# amplifier_ckt.net
KiCad netlist of a schematic drawn in EAGLE
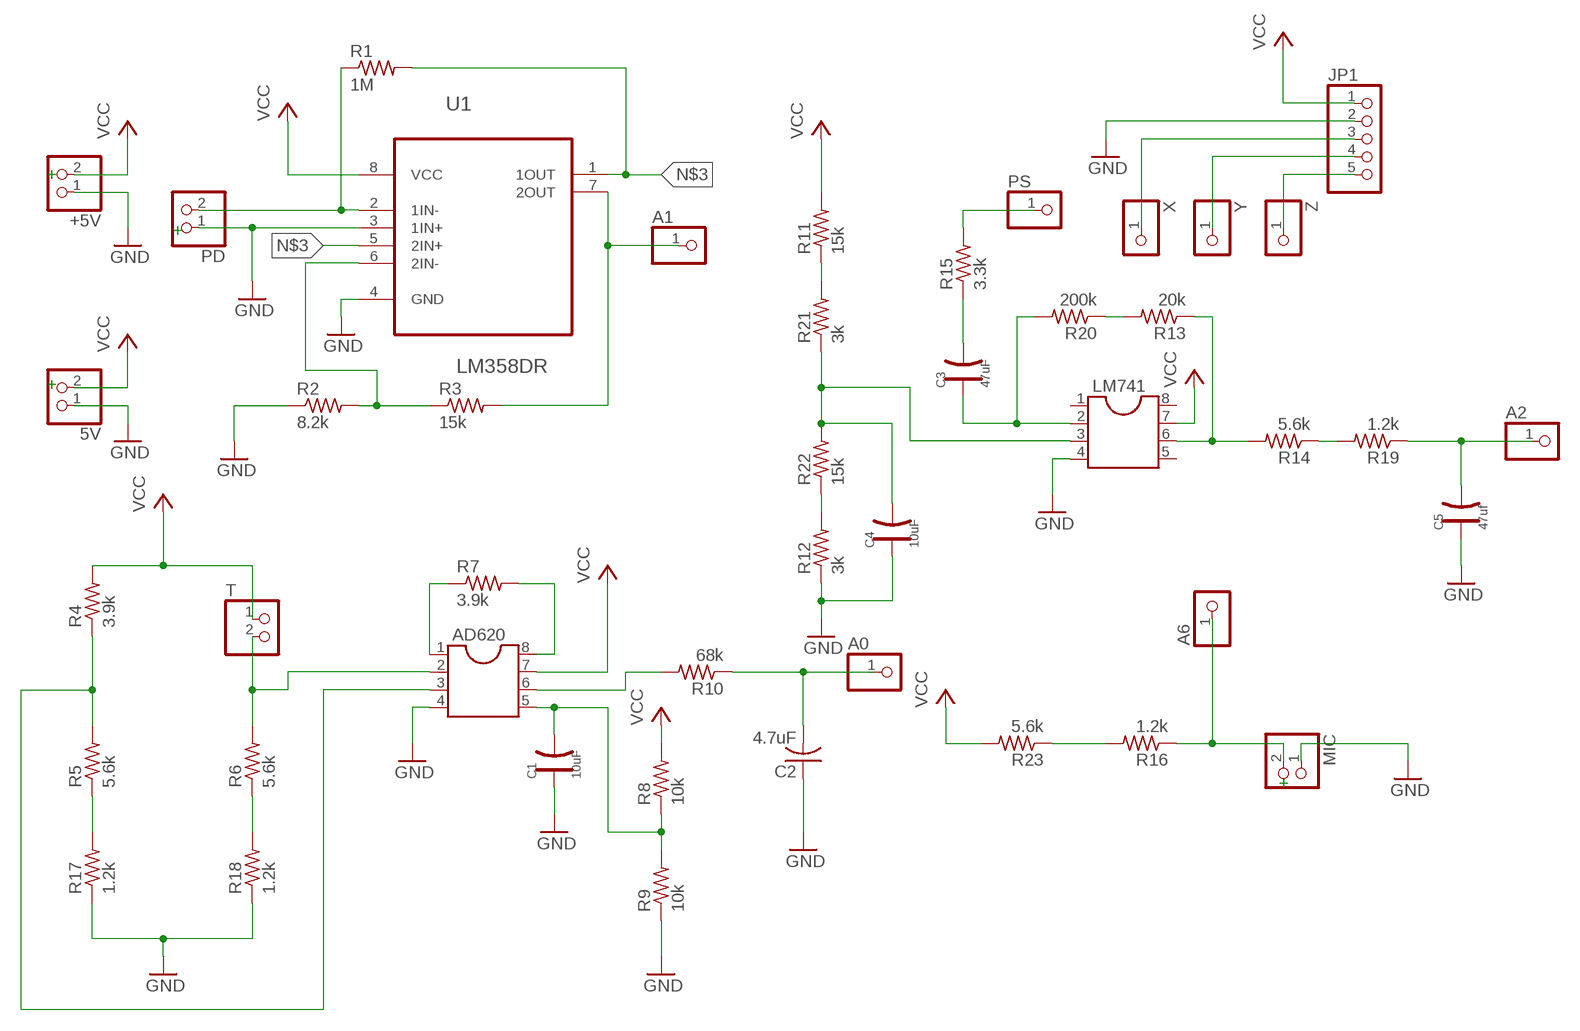
[diagram p0: schematic, sheet 1]

(export (version "E")
  (design (tool "Eeschema 10.0.6"))
  (components
    (comp (ref "+5V")
      (value "PINHD-1X2")
      (footprint "eagle-import:1X02")
      (libsource (lib "eagle-import") (part "PINHD-1X2"))
    )
    (comp (ref "5V")
      (value "PINHD-1X2")
      (footprint "eagle-import:1X02")
      (libsource (lib "eagle-import") (part "PINHD-1X2"))
    )
    (comp (ref "A0")
      (value "PINHD-1X1")
      (footprint "eagle-import:1X01")
      (libsource (lib "eagle-import") (part "PINHD-1X1"))
    )
    (comp (ref "A1")
      (value "PINHD-1X1")
      (footprint "eagle-import:1X01")
      (libsource (lib "eagle-import") (part "PINHD-1X1"))
    )
    (comp (ref "A2")
      (value "PINHD-1X1")
      (footprint "eagle-import:1X01")
      (libsource (lib "eagle-import") (part "PINHD-1X1"))
    )
    (comp (ref "A6")
      (value "PINHD-1X1")
      (footprint "eagle-import:1X01")
      (libsource (lib "eagle-import") (part "PINHD-1X1"))
    )
    (comp (ref "AD620")
      (value "DIL8S")
      (footprint "eagle-import:SOCKET-08")
      (libsource (lib "eagle-import") (part "DIL8S"))
    )
    (comp (ref "C1")
      (value "10uF")
      (footprint "eagle-import:AVX-B")
      (libsource (lib "eagle-import") (part "CAP-POLAR-AVX-B"))
    )
    (comp (ref "C2")
      (value "4.7uF")
      (footprint "eagle-import:C0805")
      (libsource (lib "eagle-import") (part "C-USC0805"))
    )
    (comp (ref "C3")
      (value "47uF")
      (footprint "eagle-import:AVX-B")
      (libsource (lib "eagle-import") (part "CAP-POLAR-AVX-B"))
    )
    (comp (ref "C4")
      (value "10uF")
      (footprint "eagle-import:AVX-B")
      (libsource (lib "eagle-import") (part "CAP-POLAR-AVX-B"))
    )
    (comp (ref "C5")
      (value "47uf")
      (footprint "eagle-import:AVX-B")
      (libsource (lib "eagle-import") (part "CAP-POLAR-AVX-B"))
    )
    (comp (ref "JP1")
      (value "PINHD-1X5")
      (footprint "eagle-import:1X05")
      (libsource (lib "eagle-import") (part "PINHD-1X5"))
    )
    (comp (ref "LM741")
      (value "DIL8S")
      (footprint "eagle-import:SOCKET-08")
      (libsource (lib "eagle-import") (part "DIL8S"))
    )
    (comp (ref "MIC")
      (value "PINHD-1X2")
      (footprint "eagle-import:1X02")
      (libsource (lib "eagle-import") (part "PINHD-1X2"))
    )
    (comp (ref "PD")
      (value "PINHD-1X2")
      (footprint "eagle-import:1X02")
      (libsource (lib "eagle-import") (part "PINHD-1X2"))
    )
    (comp (ref "PS")
      (value "PINHD-1X1")
      (footprint "eagle-import:1X01")
      (libsource (lib "eagle-import") (part "PINHD-1X1"))
    )
    (comp (ref "R1")
      (value "1M")
      (footprint "eagle-import:R0603")
      (libsource (lib "eagle-import") (part "R-US_R0603"))
    )
    (comp (ref "R2")
      (value "8.2k")
      (footprint "eagle-import:R0603")
      (libsource (lib "eagle-import") (part "R-US_R0603"))
    )
    (comp (ref "R3")
      (value "15k")
      (footprint "eagle-import:R0603")
      (libsource (lib "eagle-import") (part "R-US_R0603"))
    )
    (comp (ref "R4")
      (value "3.9k")
      (footprint "eagle-import:R0603")
      (libsource (lib "eagle-import") (part "R-US_R0603"))
    )
    (comp (ref "R5")
      (value "5.6k")
      (footprint "eagle-import:R0603")
      (libsource (lib "eagle-import") (part "R-US_R0603"))
    )
    (comp (ref "R6")
      (value "5.6k")
      (footprint "eagle-import:R0603")
      (libsource (lib "eagle-import") (part "R-US_R0603"))
    )
    (comp (ref "R7")
      (value "3.9k")
      (footprint "eagle-import:R0603")
      (libsource (lib "eagle-import") (part "R-US_R0603"))
    )
    (comp (ref "R8")
      (value "10k")
      (footprint "eagle-import:R0603")
      (libsource (lib "eagle-import") (part "R-US_R0603"))
    )
    (comp (ref "R9")
      (value "10k")
      (footprint "eagle-import:R0603")
      (libsource (lib "eagle-import") (part "R-US_R0603"))
    )
    (comp (ref "R10")
      (value "68k")
      (footprint "eagle-import:R0603")
      (libsource (lib "eagle-import") (part "R-US_R0603"))
    )
    (comp (ref "R11")
      (value "15k")
      (footprint "eagle-import:R0603")
      (libsource (lib "eagle-import") (part "R-US_R0603"))
    )
    (comp (ref "R12")
      (value "3k")
      (footprint "eagle-import:R0603")
      (libsource (lib "eagle-import") (part "R-US_R0603"))
    )
    (comp (ref "R13")
      (value "20k")
      (footprint "eagle-import:R0603")
      (libsource (lib "eagle-import") (part "R-US_R0603"))
    )
    (comp (ref "R14")
      (value "5.6k")
      (footprint "eagle-import:R0603")
      (libsource (lib "eagle-import") (part "R-US_R0603"))
    )
    (comp (ref "R15")
      (value "3.3k")
      (footprint "eagle-import:R0603")
      (libsource (lib "eagle-import") (part "R-US_R0603"))
    )
    (comp (ref "R16")
      (value "1.2k")
      (footprint "eagle-import:R0603")
      (libsource (lib "eagle-import") (part "R-US_R0603"))
    )
    (comp (ref "R17")
      (value "1.2k")
      (footprint "eagle-import:R0603")
      (libsource (lib "eagle-import") (part "R-US_R0603"))
    )
    (comp (ref "R18")
      (value "1.2k")
      (footprint "eagle-import:R0603")
      (libsource (lib "eagle-import") (part "R-US_R0603"))
    )
    (comp (ref "R19")
      (value "1.2k")
      (footprint "eagle-import:R0603")
      (libsource (lib "eagle-import") (part "R-US_R0603"))
    )
    (comp (ref "R20")
      (value "200k")
      (footprint "eagle-import:R0603")
      (libsource (lib "eagle-import") (part "R-US_R0603"))
    )
    (comp (ref "R21")
      (value "3k")
      (footprint "eagle-import:R0603")
      (libsource (lib "eagle-import") (part "R-US_R0603"))
    )
    (comp (ref "R22")
      (value "15k")
      (footprint "eagle-import:R0603")
      (libsource (lib "eagle-import") (part "R-US_R0603"))
    )
    (comp (ref "R23")
      (value "5.6k")
      (footprint "eagle-import:R0603")
      (libsource (lib "eagle-import") (part "R-US_R0603"))
    )
    (comp (ref "T")
      (value "PINHD-1X2")
      (footprint "eagle-import:1X02")
      (libsource (lib "eagle-import") (part "PINHD-1X2"))
    )
    (comp (ref "U1")
      (value "LM358DR")
      (footprint "eagle-import:SOIC127P600X175-8N")
      (libsource (lib "eagle-import") (part "LM358DR"))
    )
    (comp (ref "X")
      (value "PINHD-1X1")
      (footprint "eagle-import:1X01")
      (libsource (lib "eagle-import") (part "PINHD-1X1"))
    )
    (comp (ref "Y")
      (value "PINHD-1X1")
      (footprint "eagle-import:1X01")
      (libsource (lib "eagle-import") (part "PINHD-1X1"))
    )
    (comp (ref "Z")
      (value "PINHD-1X1")
      (footprint "eagle-import:1X01")
      (libsource (lib "eagle-import") (part "PINHD-1X1"))
    )
  )
  (nets
    (net (code "1") (name "GND") (class "Default")
      (node (ref "+5V") (pin "1") (pinfunction "1_1") (pintype "passive"))
      (node (ref "5V") (pin "1") (pinfunction "1_1") (pintype "passive"))
      (node (ref "AD620") (pin "4") (pinfunction "4_4") (pintype "passive"))
      (node (ref "C1") (pin "+") (pinfunction "+_+") (pintype "passive"))
      (node (ref "C2") (pin "1") (pinfunction "1_1") (pintype "passive"))
      (node (ref "C4") (pin "+") (pinfunction "+_+") (pintype "passive"))
      (node (ref "C5") (pin "+") (pinfunction "+_+") (pintype "passive"))
      (node (ref "JP1") (pin "2") (pinfunction "2_2") (pintype "passive"))
      (node (ref "LM741") (pin "4") (pinfunction "4_4") (pintype "passive"))
      (node (ref "MIC") (pin "1") (pinfunction "1_1") (pintype "passive"))
      (node (ref "PD") (pin "1") (pinfunction "1_1") (pintype "passive"))
      (node (ref "R12") (pin "1") (pinfunction "1_1") (pintype "passive"))
      (node (ref "R17") (pin "1") (pinfunction "1_1") (pintype "passive"))
      (node (ref "R18") (pin "1") (pinfunction "1_1") (pintype "passive"))
      (node (ref "R2") (pin "1") (pinfunction "1_1") (pintype "passive"))
      (node (ref "R9") (pin "1") (pinfunction "1_1") (pintype "passive"))
      (node (ref "U1") (pin "3") (pinfunction "1IN+_3") (pintype "input"))
      (node (ref "U1") (pin "4") (pinfunction "GND_4") (pintype "passive"))
    )
    (net (code "2") (name "N$3") (class "Default")
      (node (ref "R1") (pin "2") (pinfunction "2_2") (pintype "passive"))
      (node (ref "U1") (pin "1") (pinfunction "1OUT_1") (pintype "output"))
      (node (ref "U1") (pin "5") (pinfunction "2IN+_5") (pintype "input"))
    )
    (net (code "3") (name "Net-(A0-Pad1)") (class "Default")
      (node (ref "A0") (pin "1") (pinfunction "1_1") (pintype "passive"))
      (node (ref "C2") (pin "2") (pinfunction "2_2") (pintype "passive"))
      (node (ref "R10") (pin "1") (pinfunction "1_1") (pintype "passive"))
    )
    (net (code "4") (name "Net-(A2-Pad1)") (class "Default")
      (node (ref "A2") (pin "1") (pinfunction "1_1") (pintype "passive"))
      (node (ref "C5") (pin "-") (pinfunction "-_-") (pintype "passive"))
      (node (ref "R19") (pin "1") (pinfunction "1_1") (pintype "passive"))
    )
    (net (code "5") (name "Net-(A6-Pad1)") (class "Default")
      (node (ref "A6") (pin "1") (pinfunction "1_1") (pintype "passive"))
      (node (ref "MIC") (pin "2") (pinfunction "2_2") (pintype "passive"))
      (node (ref "R16") (pin "1") (pinfunction "1_1") (pintype "passive"))
    )
    (net (code "6") (name "Net-(AD620-Pad1)") (class "Default")
      (node (ref "AD620") (pin "1") (pinfunction "1_1") (pintype "passive"))
      (node (ref "R7") (pin "1") (pinfunction "1_1") (pintype "passive"))
    )
    (net (code "7") (name "Net-(AD620-Pad2)") (class "Default")
      (node (ref "AD620") (pin "2") (pinfunction "2_2") (pintype "passive"))
      (node (ref "R6") (pin "2") (pinfunction "2_2") (pintype "passive"))
      (node (ref "T") (pin "2") (pinfunction "2_2") (pintype "passive"))
    )
    (net (code "8") (name "Net-(AD620-Pad3)") (class "Default")
      (node (ref "AD620") (pin "3") (pinfunction "3_3") (pintype "passive"))
      (node (ref "R4") (pin "1") (pinfunction "1_1") (pintype "passive"))
      (node (ref "R5") (pin "2") (pinfunction "2_2") (pintype "passive"))
    )
    (net (code "9") (name "Net-(AD620-Pad5)") (class "Default")
      (node (ref "AD620") (pin "5") (pinfunction "5_5") (pintype "passive"))
      (node (ref "C1") (pin "-") (pinfunction "-_-") (pintype "passive"))
      (node (ref "R8") (pin "1") (pinfunction "1_1") (pintype "passive"))
      (node (ref "R9") (pin "2") (pinfunction "2_2") (pintype "passive"))
    )
    (net (code "10") (name "Net-(AD620-Pad6)") (class "Default")
      (node (ref "AD620") (pin "6") (pinfunction "6_6") (pintype "passive"))
      (node (ref "R10") (pin "2") (pinfunction "2_2") (pintype "passive"))
    )
    (net (code "11") (name "Net-(AD620-Pad8)") (class "Default")
      (node (ref "AD620") (pin "8") (pinfunction "8_8") (pintype "passive"))
      (node (ref "R7") (pin "2") (pinfunction "2_2") (pintype "passive"))
    )
    (net (code "12") (name "Net-(C3-Pad+)") (class "Default")
      (node (ref "C3") (pin "+") (pinfunction "+_+") (pintype "passive"))
      (node (ref "LM741") (pin "2") (pinfunction "2_2") (pintype "passive"))
      (node (ref "R20") (pin "2") (pinfunction "2_2") (pintype "passive"))
    )
    (net (code "13") (name "Net-(C3-Pad-)") (class "Default")
      (node (ref "C3") (pin "-") (pinfunction "-_-") (pintype "passive"))
      (node (ref "R15") (pin "1") (pinfunction "1_1") (pintype "passive"))
    )
    (net (code "14") (name "Net-(C4-Pad-)") (class "Default")
      (node (ref "C4") (pin "-") (pinfunction "-_-") (pintype "passive"))
      (node (ref "LM741") (pin "3") (pinfunction "3_3") (pintype "passive"))
      (node (ref "R21") (pin "1") (pinfunction "1_1") (pintype "passive"))
      (node (ref "R22") (pin "2") (pinfunction "2_2") (pintype "passive"))
    )
    (net (code "15") (name "Net-(JP1-Pad3)") (class "Default")
      (node (ref "JP1") (pin "3") (pinfunction "3_3") (pintype "passive"))
      (node (ref "X") (pin "1") (pinfunction "1_1") (pintype "passive"))
    )
    (net (code "16") (name "Net-(JP1-Pad4)") (class "Default")
      (node (ref "JP1") (pin "4") (pinfunction "4_4") (pintype "passive"))
      (node (ref "Y") (pin "1") (pinfunction "1_1") (pintype "passive"))
    )
    (net (code "17") (name "Net-(JP1-Pad5)") (class "Default")
      (node (ref "JP1") (pin "5") (pinfunction "5_5") (pintype "passive"))
      (node (ref "Z") (pin "1") (pinfunction "1_1") (pintype "passive"))
    )
    (net (code "18") (name "Net-(LM741-Pad6)") (class "Default")
      (node (ref "LM741") (pin "6") (pinfunction "6_6") (pintype "passive"))
      (node (ref "R13") (pin "1") (pinfunction "1_1") (pintype "passive"))
      (node (ref "R14") (pin "2") (pinfunction "2_2") (pintype "passive"))
    )
    (net (code "19") (name "Net-(PS-Pad1)") (class "Default")
      (node (ref "PS") (pin "1") (pinfunction "1_1") (pintype "passive"))
      (node (ref "R15") (pin "2") (pinfunction "2_2") (pintype "passive"))
    )
    (net (code "20") (name "Net-(R11-Pad1)") (class "Default")
      (node (ref "R11") (pin "1") (pinfunction "1_1") (pintype "passive"))
      (node (ref "R21") (pin "2") (pinfunction "2_2") (pintype "passive"))
    )
    (net (code "21") (name "Net-(R12-Pad2)") (class "Default")
      (node (ref "R12") (pin "2") (pinfunction "2_2") (pintype "passive"))
      (node (ref "R22") (pin "1") (pinfunction "1_1") (pintype "passive"))
    )
    (net (code "22") (name "Net-(R13-Pad2)") (class "Default")
      (node (ref "R13") (pin "2") (pinfunction "2_2") (pintype "passive"))
      (node (ref "R20") (pin "1") (pinfunction "1_1") (pintype "passive"))
    )
    (net (code "23") (name "Net-(R14-Pad1)") (class "Default")
      (node (ref "R14") (pin "1") (pinfunction "1_1") (pintype "passive"))
      (node (ref "R19") (pin "2") (pinfunction "2_2") (pintype "passive"))
    )
    (net (code "24") (name "Net-(R16-Pad2)") (class "Default")
      (node (ref "R16") (pin "2") (pinfunction "2_2") (pintype "passive"))
      (node (ref "R23") (pin "1") (pinfunction "1_1") (pintype "passive"))
    )
    (net (code "25") (name "Net-(R17-Pad2)") (class "Default")
      (node (ref "R17") (pin "2") (pinfunction "2_2") (pintype "passive"))
      (node (ref "R5") (pin "1") (pinfunction "1_1") (pintype "passive"))
    )
    (net (code "26") (name "Net-(R18-Pad2)") (class "Default")
      (node (ref "R18") (pin "2") (pinfunction "2_2") (pintype "passive"))
      (node (ref "R6") (pin "1") (pinfunction "1_1") (pintype "passive"))
    )
    (net (code "27") (name "Net-(U1-1IN-)") (class "Default")
      (node (ref "PD") (pin "2") (pinfunction "2_2") (pintype "passive"))
      (node (ref "R1") (pin "1") (pinfunction "1_1") (pintype "passive"))
      (node (ref "U1") (pin "2") (pinfunction "1IN-_2") (pintype "input"))
    )
    (net (code "28") (name "Net-(U1-2IN-)") (class "Default")
      (node (ref "R2") (pin "2") (pinfunction "2_2") (pintype "passive"))
      (node (ref "R3") (pin "1") (pinfunction "1_1") (pintype "passive"))
      (node (ref "U1") (pin "6") (pinfunction "2IN-_6") (pintype "input"))
    )
    (net (code "29") (name "Net-(U1-2OUT)") (class "Default")
      (node (ref "A1") (pin "1") (pinfunction "1_1") (pintype "passive"))
      (node (ref "R3") (pin "2") (pinfunction "2_2") (pintype "passive"))
      (node (ref "U1") (pin "7") (pinfunction "2OUT_7") (pintype "output"))
    )
    (net (code "30") (name "VCC") (class "Default")
      (node (ref "+5V") (pin "2") (pinfunction "2_2") (pintype "passive"))
      (node (ref "5V") (pin "2") (pinfunction "2_2") (pintype "passive"))
      (node (ref "AD620") (pin "7") (pinfunction "7_7") (pintype "passive"))
      (node (ref "JP1") (pin "1") (pinfunction "1_1") (pintype "passive"))
      (node (ref "LM741") (pin "7") (pinfunction "7_7") (pintype "passive"))
      (node (ref "R11") (pin "2") (pinfunction "2_2") (pintype "passive"))
      (node (ref "R23") (pin "2") (pinfunction "2_2") (pintype "passive"))
      (node (ref "R4") (pin "2") (pinfunction "2_2") (pintype "passive"))
      (node (ref "R8") (pin "2") (pinfunction "2_2") (pintype "passive"))
      (node (ref "T") (pin "1") (pinfunction "1_1") (pintype "passive"))
      (node (ref "U1") (pin "8") (pinfunction "VCC_8") (pintype "power_in"))
    )
    (net (code "31") (name "unconnected-(LM741-Pad1)") (class "Default")
      (node (ref "LM741") (pin "1") (pinfunction "1_1") (pintype "passive"))
    )
    (net (code "32") (name "unconnected-(LM741-Pad5)") (class "Default")
      (node (ref "LM741") (pin "5") (pinfunction "5_5") (pintype "passive"))
    )
    (net (code "33") (name "unconnected-(LM741-Pad8)") (class "Default")
      (node (ref "LM741") (pin "8") (pinfunction "8_8") (pintype "passive"))
    )
  )
)
